# LMR14050.net
KiCad netlist of a schematic drawn in Altium Designer
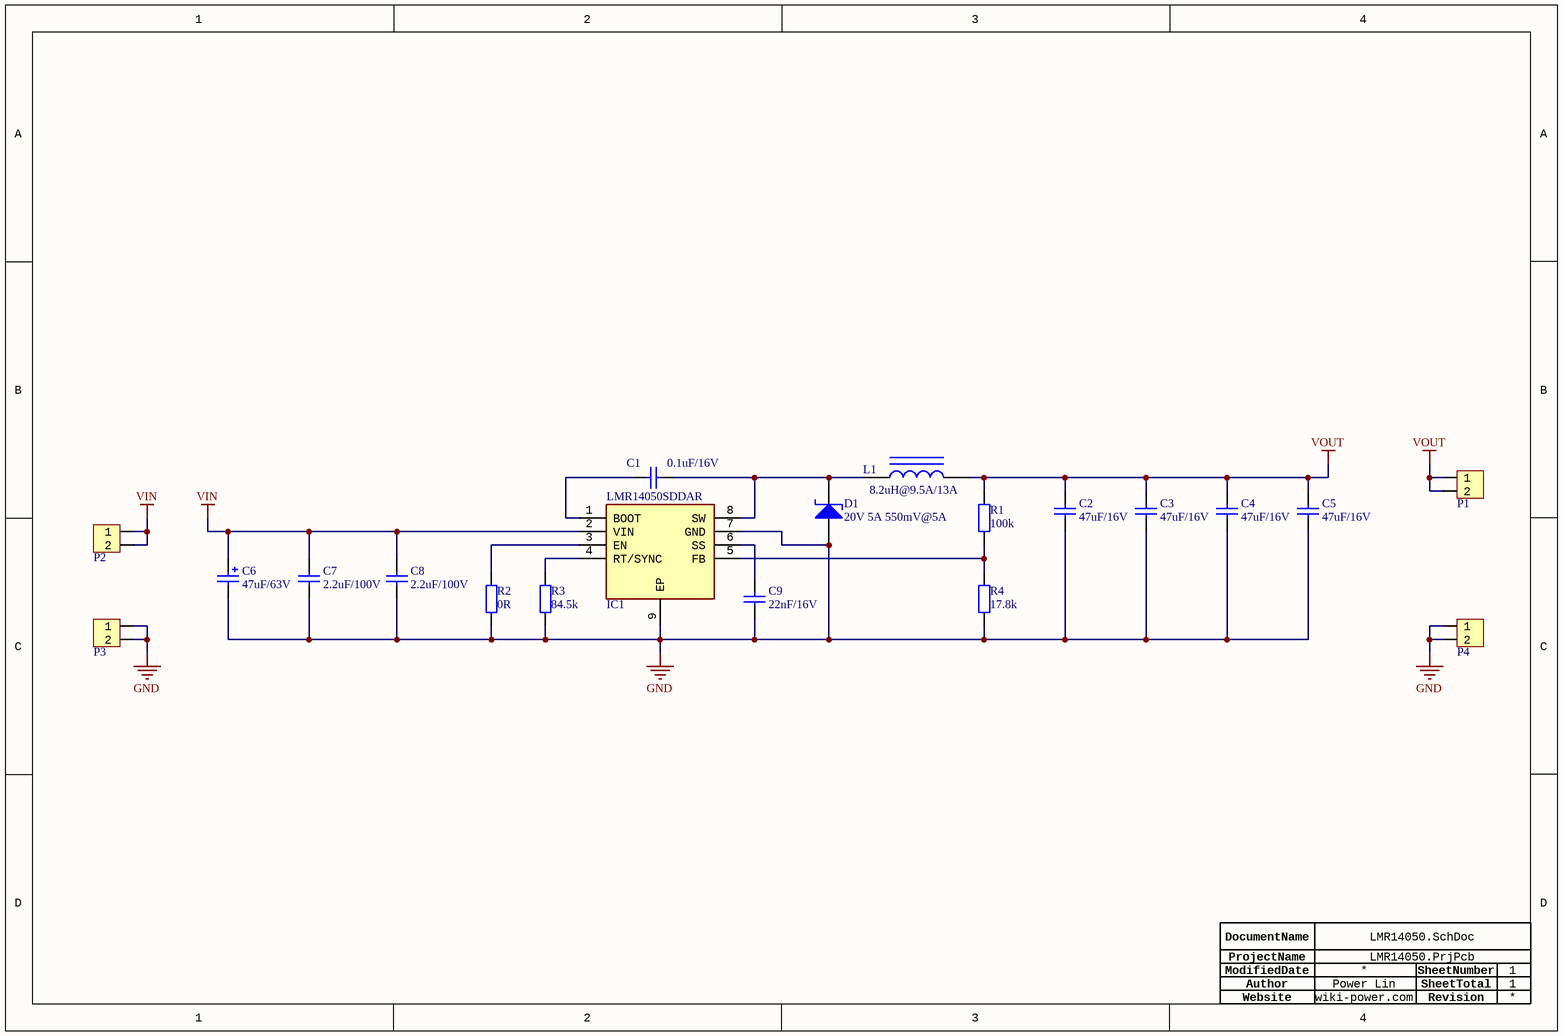
[diagram p0: LMR14050.SchDoc]

(export (version "E")
  (design (tool "Eeschema 10.0.6"))
  (components
    (comp (ref "C1")
      (value "0.1uF/16V")
      (footprint "CAP-0603")
      (description "CC0603KRX7R7BB104")
      (libsource (lib "Power_Lib_Altium") (part "CAP"))
    )
    (comp (ref "C2")
      (value "47uF/16V")
      (footprint "CAP-1210")
      (description "C1210X5R476K160NT")
      (libsource (lib "Power_Lib_Altium") (part "CAP"))
    )
    (comp (ref "C3")
      (value "47uF/16V")
      (footprint "CAP-1210")
      (description "C1210X5R476K160NT")
      (libsource (lib "Power_Lib_Altium") (part "CAP"))
    )
    (comp (ref "C4")
      (value "47uF/16V")
      (footprint "CAP-1210")
      (description "C1210X5R476K160NT")
      (libsource (lib "Power_Lib_Altium") (part "CAP"))
    )
    (comp (ref "C5")
      (value "47uF/16V")
      (footprint "CAP-1210")
      (description "C1210X5R476K160NT")
      (libsource (lib "Power_Lib_Altium") (part "CAP"))
    )
    (comp (ref "C6")
      (value "47uF/63V")
      (footprint "C_SMD-8X10")
      (description "RVT1J470M0810")
      (libsource (lib "Power_Lib_Altium") (part "CAP-POL"))
    )
    (comp (ref "C7")
      (value "2.2uF/100V")
      (footprint "CAP-1206")
      (description "CS3216X7R225K101NRI")
      (libsource (lib "Power_Lib_Altium") (part "CAP"))
    )
    (comp (ref "C8")
      (value "2.2uF/100V")
      (footprint "CAP-1206")
      (description "CS3216X7R225K101NRI")
      (libsource (lib "Power_Lib_Altium") (part "CAP"))
    )
    (comp (ref "C9")
      (value "22nF/16V")
      (footprint "CAP-0603")
      (description "CC0603KRX7R7BB223")
      (libsource (lib "Power_Lib_Altium") (part "CAP"))
    )
    (comp (ref "D1")
      (value "20V 5A 550mV@5A")
      (footprint "DO-214AB/SMC")
      (description "SS52")
      (libsource (lib "Power_Lib_Altium") (part "DIODE_Schottky"))
    )
    (comp (ref "IC1")
      (value "LMR14050SDDAR")
      (footprint "HSOIC-8")
      (fields (field (name "MOUSER PART NUMBER") "595-LMR14050SDDAR"))
      (libsource (lib "Power_Lib_Altium") (part "LMR14050SDDAR"))
    )
    (comp (ref "L1")
      (value "8.2uH@9.5A/13A")
      (footprint "SMD-13.45x12.6x4.8mm")
      (description "MDE1250-8R2M")
      (libsource (lib "Power_Lib_Altium") (part "INDUCTOR"))
    )
    (comp (ref "P1")
      (value "HDR1x2_2.54")
      (footprint "HDR1X2_2.54_180")
      (description "Header")
      (libsource (lib "Power_Lib_Altium") (part "HDR1x2_2.54"))
    )
    (comp (ref "P2")
      (value "HDR1x2_2.54")
      (footprint "HDR1X2_2.54_180")
      (description "Header")
      (libsource (lib "") (part "HDR1x2_2.54_1"))
    )
    (comp (ref "P3")
      (value "HDR1x2_2.54")
      (footprint "HDR1X2_2.54_180")
      (description "Header")
      (libsource (lib "") (part "HDR1x2_2.54_1"))
    )
    (comp (ref "P4")
      (value "HDR1x2_2.54")
      (footprint "HDR1X2_2.54_180")
      (description "Header")
      (libsource (lib "Power_Lib_Altium") (part "HDR1x2_2.54"))
    )
    (comp (ref "R1")
      (value "100k")
      (footprint "R-0603")
      (description "RC0603FR-07100KL")
      (libsource (lib "Power_Lib_Altium") (part "RES"))
    )
    (comp (ref "R2")
      (value "0R")
      (footprint "R-0603")
      (description "DNP")
      (libsource (lib "Power_Lib_Altium") (part "RES"))
    )
    (comp (ref "R3")
      (value "84.5k")
      (footprint "R-0603")
      (description "RC0603FR-0784K5L")
      (libsource (lib "Power_Lib_Altium") (part "RES"))
    )
    (comp (ref "R4")
      (value "17.8k")
      (footprint "R-0603")
      (description "RC0603FR-0717K8L")
      (libsource (lib "Power_Lib_Altium") (part "RES"))
    )
  )
  (nets
    (net (code "1") (name "GND") (class "Default")
      (node (ref "C2") (pin "1") (pinfunction "1_1") (pintype "passive"))
      (node (ref "C3") (pin "1") (pinfunction "1_1") (pintype "passive"))
      (node (ref "C4") (pin "1") (pinfunction "1_1") (pintype "passive"))
      (node (ref "C5") (pin "1") (pinfunction "1_1") (pintype "passive"))
      (node (ref "C6") (pin "2") (pinfunction "2_2") (pintype "passive"))
      (node (ref "C7") (pin "1") (pinfunction "1_1") (pintype "passive"))
      (node (ref "C8") (pin "1") (pinfunction "1_1") (pintype "passive"))
      (node (ref "C9") (pin "1") (pinfunction "1_1") (pintype "passive"))
      (node (ref "D1") (pin "1") (pinfunction "A_1") (pintype "passive"))
      (node (ref "IC1") (pin "7") (pinfunction "GND_7") (pintype "passive"))
      (node (ref "IC1") (pin "9") (pinfunction "EP_9") (pintype "passive"))
      (node (ref "P3") (pin "1") (pinfunction "1_1") (pintype "passive"))
      (node (ref "P3") (pin "2") (pinfunction "2_2") (pintype "passive"))
      (node (ref "P4") (pin "1") (pinfunction "1_1") (pintype "passive"))
      (node (ref "P4") (pin "2") (pinfunction "2_2") (pintype "passive"))
      (node (ref "R2") (pin "1") (pinfunction "1_1") (pintype "passive"))
      (node (ref "R3") (pin "1") (pinfunction "1_1") (pintype "passive"))
      (node (ref "R4") (pin "1") (pinfunction "1_1") (pintype "passive"))
    )
    (net (code "2") (name "Net-(D1-K)") (class "Default")
      (node (ref "C1") (pin "2") (pinfunction "2_2") (pintype "passive"))
      (node (ref "D1") (pin "2") (pinfunction "K_2") (pintype "passive"))
      (node (ref "IC1") (pin "8") (pinfunction "SW_8") (pintype "passive"))
      (node (ref "L1") (pin "1") (pinfunction "1_1") (pintype "passive"))
    )
    (net (code "3") (name "Net-(IC1-BOOT)") (class "Default")
      (node (ref "C1") (pin "1") (pinfunction "1_1") (pintype "passive"))
      (node (ref "IC1") (pin "1") (pinfunction "BOOT_1") (pintype "passive"))
    )
    (net (code "4") (name "Net-(IC1-EN)") (class "Default")
      (node (ref "IC1") (pin "3") (pinfunction "EN_3") (pintype "passive"))
      (node (ref "R2") (pin "2") (pinfunction "2_2") (pintype "passive"))
    )
    (net (code "5") (name "Net-(IC1-FB)") (class "Default")
      (node (ref "IC1") (pin "5") (pinfunction "FB_5") (pintype "passive"))
      (node (ref "R1") (pin "1") (pinfunction "1_1") (pintype "passive"))
      (node (ref "R4") (pin "2") (pinfunction "2_2") (pintype "passive"))
    )
    (net (code "6") (name "Net-(IC1-RT{slash}SYNC)") (class "Default")
      (node (ref "IC1") (pin "4") (pinfunction "RT/SYNC_4") (pintype "passive"))
      (node (ref "R3") (pin "2") (pinfunction "2_2") (pintype "passive"))
    )
    (net (code "7") (name "Net-(IC1-SS)") (class "Default")
      (node (ref "C9") (pin "2") (pinfunction "2_2") (pintype "passive"))
      (node (ref "IC1") (pin "6") (pinfunction "SS_6") (pintype "passive"))
    )
    (net (code "8") (name "VIN") (class "Default")
      (node (ref "C6") (pin "1") (pinfunction "1_1") (pintype "passive"))
      (node (ref "C7") (pin "2") (pinfunction "2_2") (pintype "passive"))
      (node (ref "C8") (pin "2") (pinfunction "2_2") (pintype "passive"))
      (node (ref "IC1") (pin "2") (pinfunction "VIN_2") (pintype "passive"))
      (node (ref "P2") (pin "1") (pinfunction "1_1") (pintype "passive"))
      (node (ref "P2") (pin "2") (pinfunction "2_2") (pintype "passive"))
    )
    (net (code "9") (name "VOUT") (class "Default")
      (node (ref "C2") (pin "2") (pinfunction "2_2") (pintype "passive"))
      (node (ref "C3") (pin "2") (pinfunction "2_2") (pintype "passive"))
      (node (ref "C4") (pin "2") (pinfunction "2_2") (pintype "passive"))
      (node (ref "C5") (pin "2") (pinfunction "2_2") (pintype "passive"))
      (node (ref "L1") (pin "2") (pinfunction "2_2") (pintype "passive"))
      (node (ref "P1") (pin "1") (pinfunction "1_1") (pintype "passive"))
      (node (ref "P1") (pin "2") (pinfunction "2_2") (pintype "passive"))
      (node (ref "R1") (pin "2") (pinfunction "2_2") (pintype "passive"))
    )
  )
)
